# 15_BoardPowerSupply.net
KiCad netlist of a schematic drawn in Altium Designer
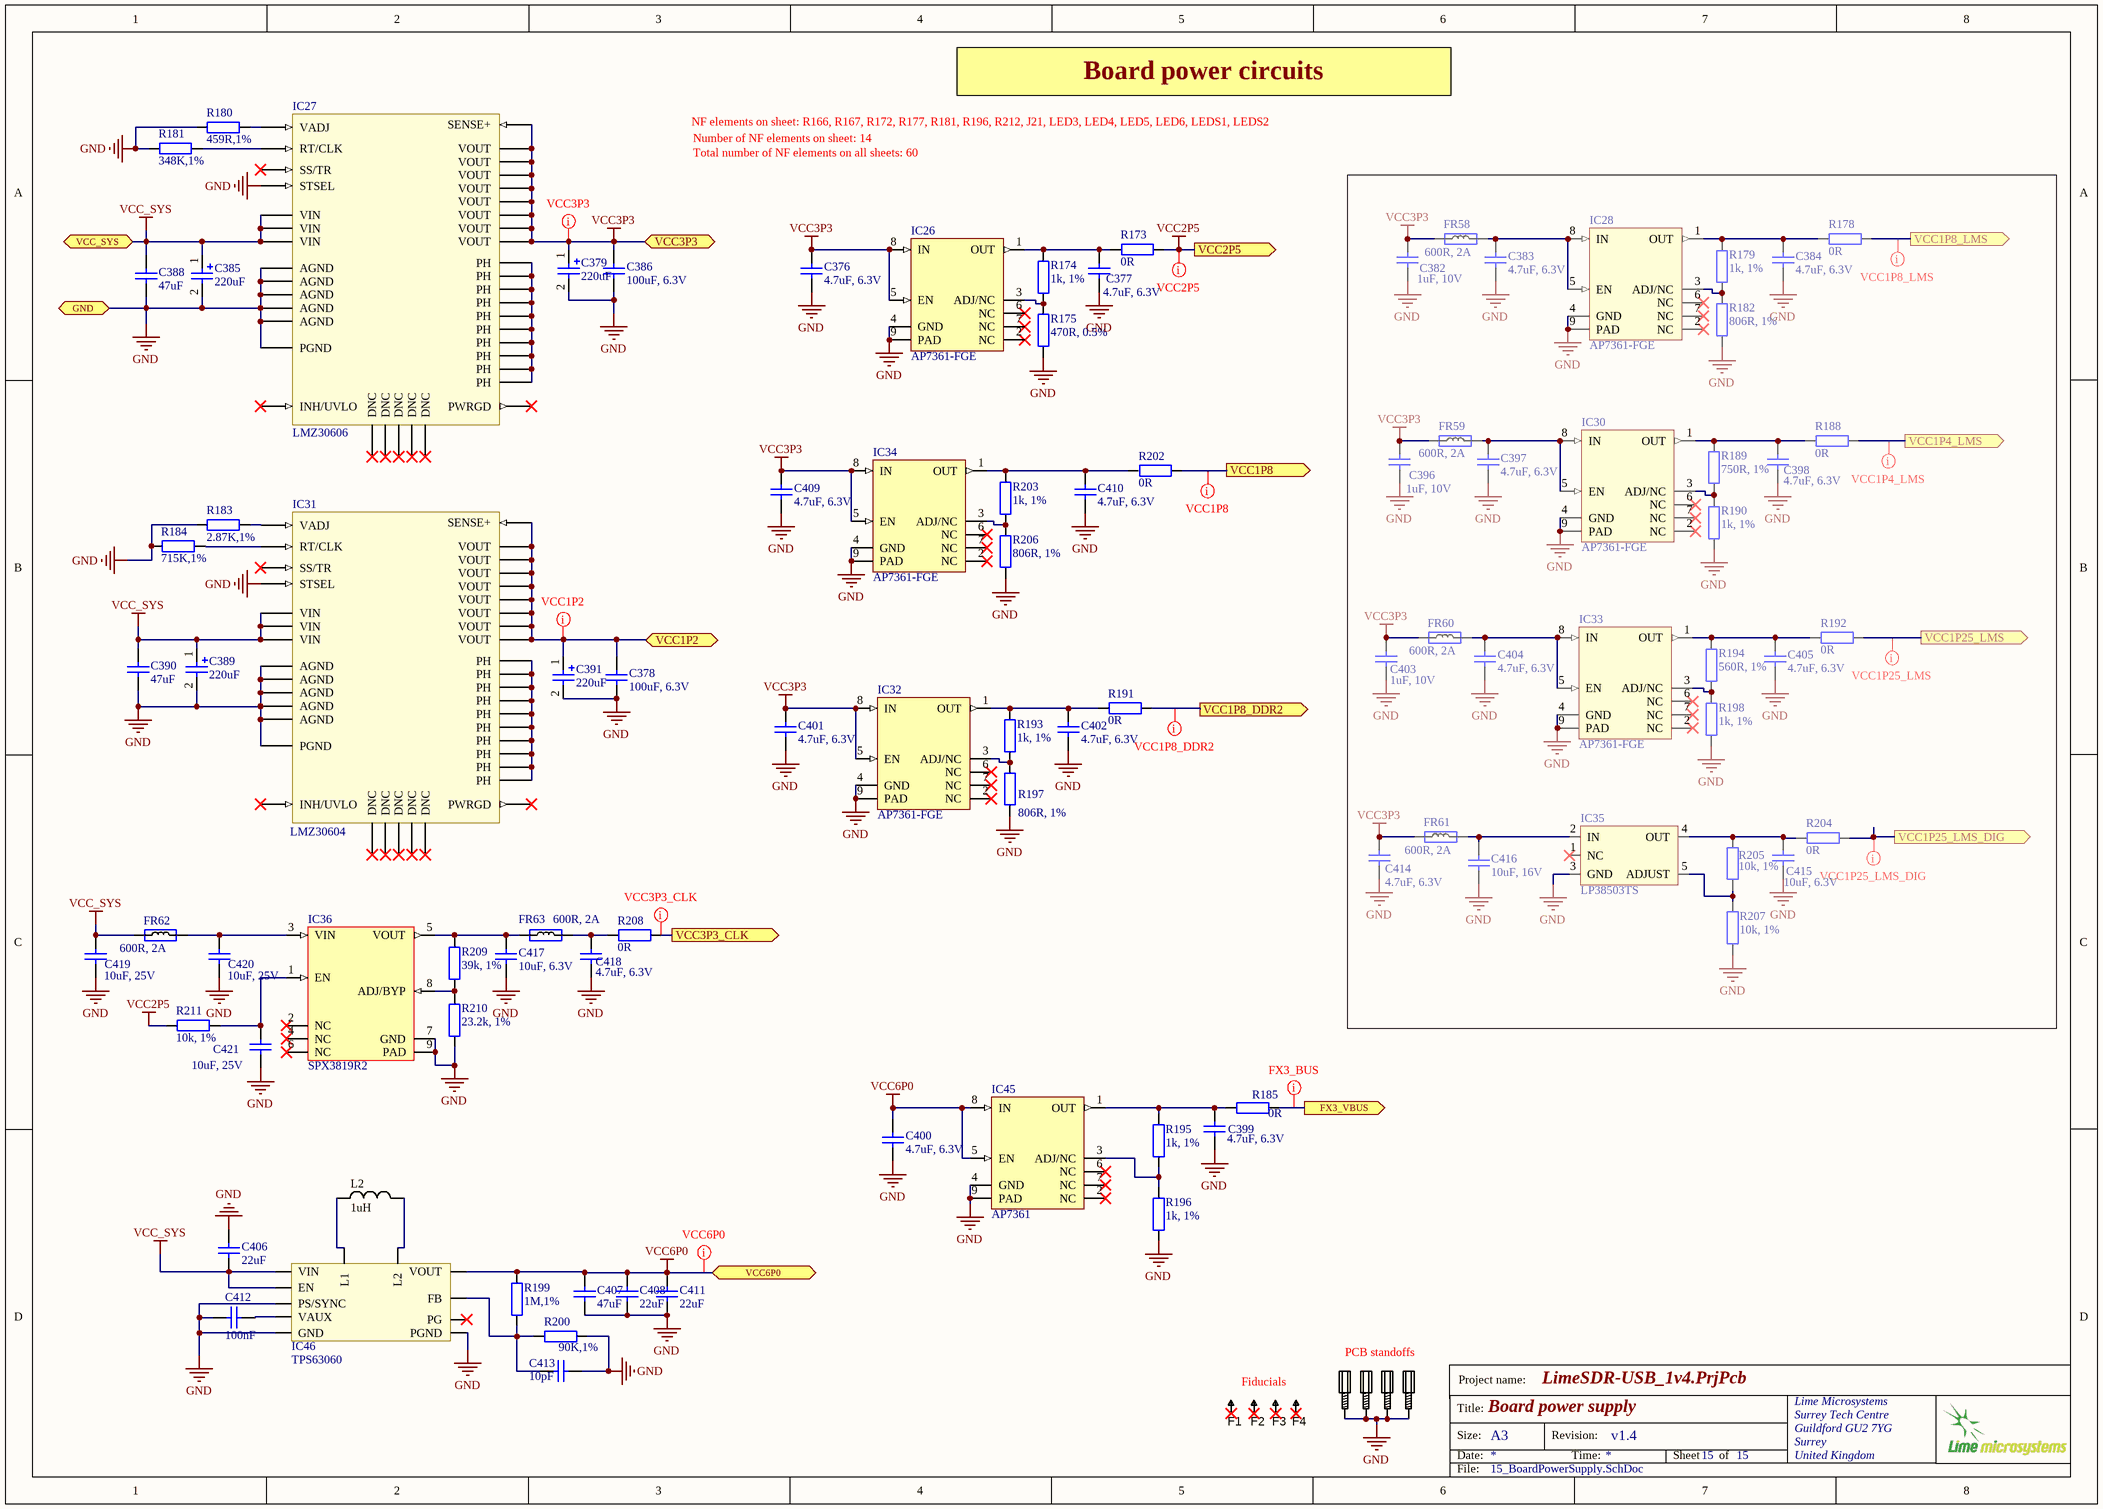
[diagram p0: 15_BoardPowerSupply.SchDoc]

(export (version "E")
  (design (tool "Eeschema 10.0.6"))
  (components
    (comp (ref "C376")
      (value "4.7uF, 6.3V")
      (footprint "CAP0402")
      (fields
        (field (name "MANUFACTURER") "Murata Electronics North America")
        (field (name "TOLERANCE") "±20%")
        (field (name "MANUFACTURER PART NUMBER") "GRM155R60J475ME87D")
      )
      (libsource (lib "LimeMicroAltiumLib_schLib") (part "Cap_0402"))
    )
    (comp (ref "C377")
      (value "4.7uF, 6.3V")
      (footprint "CAP0402")
      (fields
        (field (name "MANUFACTURER") "Murata Electronics North America")
        (field (name "TOLERANCE") "±20%")
        (field (name "MANUFACTURER PART NUMBER") "GRM155R60J475ME87D")
      )
      (libsource (lib "LimeMicroAltiumLib_schLib") (part "Cap_0402"))
    )
    (comp (ref "C378")
      (value "100uF, 6.3V")
      (footprint "CAP1206")
      (fields (field (name "MANUFACTURER") "Murata Electronics North America"))
      (libsource (lib "LimeFPGAboard_schLib") (part "Cap_1206"))
    )
    (comp (ref "C379") (value "220uF") (libsource (lib "LimeMicroAltiumLib_schLib") (part "Cap_pol_1206")))
    (comp (ref "C382")
      (value "1uF, 10V")
      (footprint "CAP0402")
      (fields (field (name "MANUFACTURER") "TDK"))
      (libsource (lib "LimeMicroAltiumLib_schLib") (part "Cap_0402"))
    )
    (comp (ref "C383")
      (value "4.7uF, 6.3V")
      (footprint "CAP0402")
      (fields
        (field (name "MANUFACTURER") "Murata Electronics North America")
        (field (name "TOLERANCE") "±20%")
        (field (name "MANUFACTURER PART NUMBER") "GRM155R60J475ME87D")
      )
      (libsource (lib "LimeMicroAltiumLib_schLib") (part "Cap_0402"))
    )
    (comp (ref "C384")
      (value "4.7uF, 6.3V")
      (footprint "CAP0402")
      (fields
        (field (name "MANUFACTURER") "Murata Electronics North America")
        (field (name "TOLERANCE") "±20%")
        (field (name "MANUFACTURER PART NUMBER") "GRM155R60J475ME87D")
      )
      (libsource (lib "LimeMicroAltiumLib_schLib") (part "Cap_0402"))
    )
    (comp (ref "C385") (value "220uF") (libsource (lib "LimeMicroAltiumLib_schLib") (part "Cap_pol_1206")))
    (comp (ref "C386")
      (value "100uF, 6.3V")
      (footprint "CAP1206")
      (fields (field (name "MANUFACTURER") "Murata Electronics North America"))
      (libsource (lib "LimeFPGAboard_schLib") (part "Cap_1206"))
    )
    (comp (ref "C388")
      (value "47uF")
      (footprint "CAP1206")
      (libsource (lib "LimeMicroAltiumLib_schLib") (part "Cap_1206"))
    )
    (comp (ref "C389") (value "220uF") (libsource (lib "LimeMicroAltiumLib_schLib") (part "Cap_pol_1206")))
    (comp (ref "C390")
      (value "47uF")
      (footprint "CAP1206")
      (fields (field (name "MANUFACTURER") "Murata Electronics North America"))
      (libsource (lib "LimeFPGAboard_schLib") (part "Cap_1206"))
    )
    (comp (ref "C391") (value "220uF") (libsource (lib "LimeMicroAltiumLib_schLib") (part "Cap_pol_1206")))
    (comp (ref "C396")
      (value "1uF, 10V")
      (footprint "CAP0402")
      (fields (field (name "MANUFACTURER") "TDK"))
      (libsource (lib "LimeMicroAltiumLib_schLib") (part "Cap_0402"))
    )
    (comp (ref "C397")
      (value "4.7uF, 6.3V")
      (footprint "CAP0402")
      (fields
        (field (name "MANUFACTURER") "Murata Electronics North America")
        (field (name "TOLERANCE") "±20%")
        (field (name "MANUFACTURER PART NUMBER") "GRM155R60J475ME87D")
      )
      (libsource (lib "LimeMicroAltiumLib_schLib") (part "Cap_0402"))
    )
    (comp (ref "C398")
      (value "4.7uF, 6.3V")
      (footprint "CAP0402")
      (fields
        (field (name "MANUFACTURER") "Murata Electronics North America")
        (field (name "TOLERANCE") "±20%")
        (field (name "MANUFACTURER PART NUMBER") "GRM155R60J475ME87D")
      )
      (libsource (lib "LimeMicroAltiumLib_schLib") (part "Cap_0402"))
    )
    (comp (ref "C399")
      (value "4.7uF, 6.3V")
      (footprint "CAP0402")
      (fields
        (field (name "MANUFACTURER") "Murata Electronics North America")
        (field (name "TOLERANCE") "±20%")
        (field (name "MANUFACTURER PART NUMBER") "GRM155R60J475ME87D")
      )
      (libsource (lib "LimeMicroAltiumLib_schLib") (part "Cap_0402"))
    )
    (comp (ref "C400")
      (value "4.7uF, 6.3V")
      (footprint "CAP0402")
      (fields
        (field (name "MANUFACTURER") "Murata Electronics North America")
        (field (name "TOLERANCE") "±20%")
        (field (name "MANUFACTURER PART NUMBER") "GRM155R60J475ME87D")
      )
      (libsource (lib "LimeMicroAltiumLib_schLib") (part "Cap_0402"))
    )
    (comp (ref "C401")
      (value "4.7uF, 6.3V")
      (footprint "CAP0402")
      (fields
        (field (name "MANUFACTURER") "Murata Electronics North America")
        (field (name "TOLERANCE") "±20%")
        (field (name "MANUFACTURER PART NUMBER") "GRM155R60J475ME87D")
      )
      (libsource (lib "LimeMicroAltiumLib_schLib") (part "Cap_0402"))
    )
    (comp (ref "C402")
      (value "4.7uF, 6.3V")
      (footprint "CAP0402")
      (fields
        (field (name "MANUFACTURER") "Murata Electronics North America")
        (field (name "TOLERANCE") "±20%")
        (field (name "MANUFACTURER PART NUMBER") "GRM155R60J475ME87D")
      )
      (libsource (lib "LimeMicroAltiumLib_schLib") (part "Cap_0402"))
    )
    (comp (ref "C403")
      (value "1uF, 10V")
      (footprint "CAP0402")
      (fields (field (name "MANUFACTURER") "TDK"))
      (libsource (lib "LimeMicroAltiumLib_schLib") (part "Cap_0402"))
    )
    (comp (ref "C404")
      (value "4.7uF, 6.3V")
      (footprint "CAP0402")
      (fields
        (field (name "MANUFACTURER") "Murata Electronics North America")
        (field (name "TOLERANCE") "±20%")
        (field (name "MANUFACTURER PART NUMBER") "GRM155R60J475ME87D")
      )
      (libsource (lib "LimeMicroAltiumLib_schLib") (part "Cap_0402"))
    )
    (comp (ref "C405")
      (value "4.7uF, 6.3V")
      (footprint "CAP0402")
      (fields
        (field (name "MANUFACTURER") "Murata Electronics North America")
        (field (name "TOLERANCE") "±20%")
        (field (name "MANUFACTURER PART NUMBER") "GRM155R60J475ME87D")
      )
      (libsource (lib "LimeMicroAltiumLib_schLib") (part "Cap_0402"))
    )
    (comp (ref "C406")
      (value "22uF")
      (footprint "CAP1206")
      (libsource (lib "LimeMicroAltiumLib_schLib") (part "Cap_1206"))
    )
    (comp (ref "C407")
      (value "47uF")
      (footprint "CAP1206")
      (libsource (lib "LimeMicroAltiumLib_schLib") (part "Cap_1206"))
    )
    (comp (ref "C408")
      (value "22uF")
      (footprint "CAP1206")
      (libsource (lib "LimeMicroAltiumLib_schLib") (part "Cap_1206"))
    )
    (comp (ref "C409")
      (value "4.7uF, 6.3V")
      (footprint "CAP0402")
      (fields
        (field (name "MANUFACTURER") "Murata Electronics North America")
        (field (name "TOLERANCE") "±20%")
        (field (name "MANUFACTURER PART NUMBER") "GRM155R60J475ME87D")
      )
      (libsource (lib "LimeMicroAltiumLib_schLib") (part "Cap_0402"))
    )
    (comp (ref "C410")
      (value "4.7uF, 6.3V")
      (footprint "CAP0402")
      (fields
        (field (name "MANUFACTURER") "Murata Electronics North America")
        (field (name "TOLERANCE") "±20%")
        (field (name "MANUFACTURER PART NUMBER") "GRM155R60J475ME87D")
      )
      (libsource (lib "LimeMicroAltiumLib_schLib") (part "Cap_0402"))
    )
    (comp (ref "C411")
      (value "22uF")
      (footprint "CAP1206")
      (libsource (lib "LimeMicroAltiumLib_schLib") (part "Cap_1206"))
    )
    (comp (ref "C412")
      (value "100nF")
      (footprint "CAP0603")
      (libsource (lib "LimeMicroAltiumLib_schLib") (part "Cap_0603"))
    )
    (comp (ref "C413")
      (value "10pF")
      (footprint "CAP0603")
      (libsource (lib "LimeMicroAltiumLib_schLib") (part "Cap_0603"))
    )
    (comp (ref "C414")
      (value "4.7uF, 6.3V")
      (footprint "CAP0402")
      (fields
        (field (name "MANUFACTURER") "Murata Electronics North America")
        (field (name "TOLERANCE") "±20%")
        (field (name "MANUFACTURER PART NUMBER") "GRM155R60J475ME87D")
      )
      (libsource (lib "LimeMicroAltiumLib_schLib") (part "Cap_0402"))
    )
    (comp (ref "C415")
      (value "10uF, 6.3V")
      (footprint "CAP0603")
      (fields (field (name "TOLERANCE") "±20%") (field (name "MANUFACTURER") "Yageo"))
      (libsource (lib "LimeFPGAboard_schLib") (part "Cap_0603"))
    )
    (comp (ref "C416")
      (value "10uF, 16V")
      (footprint "CAP0603")
      (fields (field (name "MANUFACTURER") "Yageo") (field (name "TOLERANCE") "±20%"))
      (libsource (lib "LimeMicroAltiumLib_schLib") (part "Cap_0603"))
    )
    (comp (ref "C417")
      (value "10uF, 6.3V")
      (footprint "CAP0603")
      (fields (field (name "TOLERANCE") "±20%") (field (name "MANUFACTURER") "Yageo"))
      (libsource (lib "LimeFPGAboard_schLib") (part "Cap_0603"))
    )
    (comp (ref "C418")
      (value "4.7uF, 6.3V")
      (footprint "CAP0402")
      (fields
        (field (name "MANUFACTURER") "Murata Electronics North America")
        (field (name "TOLERANCE") "±20%")
        (field (name "MANUFACTURER PART NUMBER") "GRM155R60J475ME87D")
      )
      (libsource (lib "LimeMicroAltiumLib_schLib") (part "Cap_0402"))
    )
    (comp (ref "C419")
      (value "10uF, 25V")
      (footprint "CAP0603")
      (fields
        (field (name "MANUFACTURER") "Murata Electronics North America")
        (field (name "MANUFACTURER PART NUMBER") "GRM188R61E106MA73D")
        (field (name "TOLERANCE") "±20%")
      )
      (libsource (lib "LimeMicroAltiumLib_schLib") (part "Cap_0603"))
    )
    (comp (ref "C420")
      (value "10uF, 25V")
      (footprint "CAP0603")
      (fields
        (field (name "MANUFACTURER") "Murata Electronics North America")
        (field (name "MANUFACTURER PART NUMBER") "GRM188R61E106MA73D")
        (field (name "TOLERANCE") "±20%")
      )
      (libsource (lib "LimeMicroAltiumLib_schLib") (part "Cap_0603"))
    )
    (comp (ref "C421")
      (value "10uF, 25V")
      (footprint "CAP0603")
      (fields
        (field (name "MANUFACTURER") "Murata Electronics North America")
        (field (name "MANUFACTURER PART NUMBER") "GRM188R61E106MA73D")
        (field (name "TOLERANCE") "±20%")
      )
      (libsource (lib "LimeMicroAltiumLib_schLib") (part "Cap_0603"))
    )
    (comp (ref "F1")
      (value "Fiducial")
      (footprint "Fiducial")
      (libsource (lib "VGTU_Altium_lib") (part "Fiducial"))
    )
    (comp (ref "F2")
      (value "Fiducial")
      (footprint "Fiducial")
      (libsource (lib "VGTU_Altium_lib") (part "Fiducial"))
    )
    (comp (ref "F3")
      (value "Fiducial")
      (footprint "Fiducial")
      (libsource (lib "VGTU_Altium_lib") (part "Fiducial"))
    )
    (comp (ref "F4")
      (value "Fiducial")
      (footprint "Fiducial")
      (libsource (lib "VGTU_Altium_lib") (part "Fiducial"))
    )
    (comp (ref "FR58")
      (value "600R, 2A")
      (footprint "RES0805")
      (fields (field (name "MANUFACTURER") "TDK Corporation"))
      (libsource (lib "LimeMicroAltiumLib_schLib") (part "Ferrite"))
    )
    (comp (ref "FR59")
      (value "600R, 2A")
      (footprint "RES0805")
      (fields (field (name "MANUFACTURER") "TDK Corporation"))
      (libsource (lib "LimeMicroAltiumLib_schLib") (part "Ferrite"))
    )
    (comp (ref "FR60")
      (value "600R, 2A")
      (footprint "RES0805")
      (fields (field (name "MANUFACTURER") "TDK Corporation"))
      (libsource (lib "LimeMicroAltiumLib_schLib") (part "Ferrite"))
    )
    (comp (ref "FR61")
      (value "600R, 2A")
      (footprint "RES0805")
      (fields (field (name "MANUFACTURER") "TDK Corporation"))
      (libsource (lib "LimeMicroAltiumLib_schLib") (part "Ferrite"))
    )
    (comp (ref "FR62")
      (value "600R, 2A")
      (footprint "RES0805")
      (fields (field (name "MANUFACTURER") "TDK Corporation"))
      (libsource (lib "LimeMicroAltiumLib_schLib") (part "Ferrite"))
    )
    (comp (ref "FR63")
      (value "600R, 2A")
      (footprint "RES0805")
      (fields (field (name "MANUFACTURER") "TDK Corporation"))
      (libsource (lib "LimeMicroAltiumLib_schLib") (part "Ferrite"))
    )
    (comp (ref "IC26")
      (value "AP7361-FGE")
      (footprint "AP7361")
      (fields
        (field (name "MANUFACTURER PART NUMBER") "AP7361-FGE-7")
        (field (name "MANUFACTURER") "Diodes Incorporated")
      )
      (libsource (lib "LimeMicroAltiumLib_schLib") (part "AP7361"))
    )
    (comp (ref "IC27")
      (value "LMZ30606")
      (footprint "QFN-LMZ306xx")
      (libsource (lib "LimeMicroAltiumLib_schLib") (part "LMZ30606"))
    )
    (comp (ref "IC28")
      (value "AP7361-FGE")
      (footprint "AP7361")
      (fields
        (field (name "MANUFACTURER PART NUMBER") "AP7361-FGE-7")
        (field (name "MANUFACTURER") "Diodes Incorporated")
      )
      (libsource (lib "LimeMicroAltiumLib_schLib") (part "AP7361"))
    )
    (comp (ref "IC30")
      (value "AP7361-FGE")
      (footprint "AP7361")
      (fields
        (field (name "MANUFACTURER PART NUMBER") "AP7361-FGE-7")
        (field (name "MANUFACTURER") "Diodes Incorporated")
      )
      (libsource (lib "LimeMicroAltiumLib_schLib") (part "AP7361"))
    )
    (comp (ref "IC31")
      (value "LMZ30604")
      (footprint "QFN-LMZ306xx")
      (libsource (lib "LimeMicroAltiumLib_schLib") (part "LMZ30604"))
    )
    (comp (ref "IC32")
      (value "AP7361-FGE")
      (footprint "AP7361")
      (fields
        (field (name "MANUFACTURER PART NUMBER") "AP7361-FGE-7")
        (field (name "MANUFACTURER") "Diodes Incorporated")
      )
      (libsource (lib "LimeMicroAltiumLib_schLib") (part "AP7361"))
    )
    (comp (ref "IC33")
      (value "AP7361-FGE")
      (footprint "AP7361")
      (fields
        (field (name "MANUFACTURER PART NUMBER") "AP7361-FGE-7")
        (field (name "MANUFACTURER") "Diodes Incorporated")
      )
      (libsource (lib "LimeMicroAltiumLib_schLib") (part "AP7361"))
    )
    (comp (ref "IC34")
      (value "AP7361-FGE")
      (footprint "AP7361")
      (fields
        (field (name "MANUFACTURER PART NUMBER") "AP7361-FGE-7")
        (field (name "MANUFACTURER") "Diodes Incorporated")
      )
      (libsource (lib "LimeMicroAltiumLib_schLib") (part "AP7361"))
    )
    (comp (ref "IC35")
      (value "LP38503TS")
      (footprint "TO-263-5_v2")
      (fields
        (field (name "MANUFACTURER PART NUMBER") "LP38503TS-ADJ/NOPB")
        (field (name "MANUFACTURER") "Texas Instruments")
      )
      (libsource (lib "LimeMicroAltiumLib_schLib") (part "LP38503TS"))
    )
    (comp (ref "IC36")
      (value "SPX3819R2")
      (footprint "SPX3819R2-L/TR")
      (fields (field (name "MANUFACTURER") "Exar Corporation"))
      (libsource (lib "LimeMicroAltiumLib_schLib") (part "SPX3819R2-L/TR"))
    )
    (comp (ref "IC45")
      (value "AP7361")
      (footprint "AP7361")
      (fields (field (name "MANUFACTURER") "Diodes Incorporated"))
      (libsource (lib "LimeMicroAltiumLib_schLib") (part "AP7361"))
    )
    (comp (ref "IC46")
      (value "TPS63060")
      (footprint "SON-10")
      (libsource (lib "LimeMicroAltiumLib_schLib") (part "TPS63060"))
    )
    (comp (ref "L2")
      (value "1uH")
      (footprint "FDVE1040_TOKO_INDUCTOR")
      (fields (field (name "TOLERANCE") "±20%") (field (name "MANUFACTURER") "Vishay Dale"))
      (libsource (lib "LimeMicroAltiumLib_schLib") (part "Inductor_0603"))
    )
    (comp (ref "MECH1")
      (value "# pcs.")
      (footprint "PCB_standoff")
      (description "STANDOFF M/F MET 5MM HEX 10MM L")
      (fields (field (name "MANUFACTURER") "FIX&FASTEN"))
      (libsource (lib "LimeMicroAltiumLib_schLib") (part "STANDOFF_M-F_THREADED_M3x8x10mm_HEX_5mm dia"))
    )
    (comp (ref "MECH2")
      (value "# pcs.")
      (footprint "PCB_standoff")
      (description "STANDOFF M/F MET 5MM HEX 10MM L")
      (fields (field (name "MANUFACTURER") "FIX&FASTEN"))
      (libsource (lib "LimeMicroAltiumLib_schLib") (part "STANDOFF_M-F_THREADED_M3x8x10mm_HEX_5mm dia"))
    )
    (comp (ref "MECH3")
      (value "# pcs.")
      (footprint "PCB_standoff")
      (description "STANDOFF M/F MET 5MM HEX 10MM L")
      (fields (field (name "MANUFACTURER") "FIX&FASTEN"))
      (libsource (lib "LimeMicroAltiumLib_schLib") (part "STANDOFF_M-F_THREADED_M3x8x10mm_HEX_5mm dia"))
    )
    (comp (ref "MECH4")
      (value "# pcs.")
      (footprint "PCB_standoff")
      (description "STANDOFF M/F MET 5MM HEX 10MM L")
      (fields (field (name "MANUFACTURER") "FIX&FASTEN"))
      (libsource (lib "LimeMicroAltiumLib_schLib") (part "STANDOFF_M-F_THREADED_M3x8x10mm_HEX_5mm dia"))
    )
    (comp (ref "R173")
      (value "0R")
      (footprint "RES0402")
      (fields (field (name "MANUFACTURER") "Yageo") (field (name "TOLERANCE") "Jumper"))
      (libsource (lib "LimeMicroAltiumLib_schLib") (part "Res_0402"))
    )
    (comp (ref "R174")
      (value "1k, 1%")
      (footprint "RES0402")
      (fields (field (name "MANUFACTURER") "Stackpole Electronics Inc") (field (name "TOLERANCE") "±1%"))
      (libsource (lib "LimeMicroAltiumLib_schLib") (part "Res_0402"))
    )
    (comp (ref "R175")
      (value "470R, 0.5%")
      (footprint "RES0402")
      (fields
        (field (name "TOLERANCE") "±0.5%")
        (field (name "MANUFACTURER") "Panasonic Electronic Components")
      )
      (libsource (lib "LimeMicroAltiumLib_schLib") (part "Res_0402"))
    )
    (comp (ref "R178")
      (value "0R")
      (footprint "RES0402")
      (fields (field (name "MANUFACTURER") "Yageo") (field (name "TOLERANCE") "Jumper"))
      (libsource (lib "LimeMicroAltiumLib_schLib") (part "Res_0402"))
    )
    (comp (ref "R179")
      (value "1k, 1%")
      (footprint "RES0402")
      (fields (field (name "MANUFACTURER") "Stackpole Electronics Inc") (field (name "TOLERANCE") "±1%"))
      (libsource (lib "LimeMicroAltiumLib_schLib") (part "Res_0402"))
    )
    (comp (ref "R180")
      (value "459R,1%")
      (footprint "RES0402")
      (fields (field (name "MANUFACTURER") "Yageo") (field (name "TOLERANCE") "±1%"))
      (libsource (lib "LimeMicroAltiumLib_schLib") (part "Res_0402"))
    )
    (comp (ref "R181")
      (value "348K,1%")
      (footprint "RES0402")
      (fields (field (name "MANUFACTURER") "Yageo") (field (name "TOLERANCE") "±1%"))
      (libsource (lib "LimeMicroAltiumLib_schLib") (part "Res_0402"))
    )
    (comp (ref "R182")
      (value "806R, 1%")
      (footprint "RES0402")
      (fields (field (name "TOLERANCE") "±1%") (field (name "MANUFACTURER") "Stackpole Electronics Inc"))
      (libsource (lib "LimeMicroAltiumLib_schLib") (part "Res_0402"))
    )
    (comp (ref "R183")
      (value "2.87K,1%")
      (footprint "RES0402")
      (fields (field (name "MANUFACTURER") "Yageo") (field (name "TOLERANCE") "±1%"))
      (libsource (lib "LimeMicroAltiumLib_schLib") (part "Res_0402"))
    )
    (comp (ref "R184")
      (value "715K,1%")
      (footprint "RES0402")
      (fields (field (name "MANUFACTURER") "Yageo") (field (name "TOLERANCE") "±1%"))
      (libsource (lib "LimeMicroAltiumLib_schLib") (part "Res_0402"))
    )
    (comp (ref "R185")
      (value "0R")
      (footprint "RES0402")
      (fields (field (name "MANUFACTURER") "Yageo") (field (name "TOLERANCE") "Jumper"))
      (libsource (lib "LimeMicroAltiumLib_schLib") (part "Res_0402"))
    )
    (comp (ref "R188")
      (value "0R")
      (footprint "RES0402")
      (fields (field (name "MANUFACTURER") "Yageo") (field (name "TOLERANCE") "Jumper"))
      (libsource (lib "LimeMicroAltiumLib_schLib") (part "Res_0402"))
    )
    (comp (ref "R189")
      (value "750R, 1%")
      (footprint "RES0402")
      (fields
        (field (name "TOLERANCE") "±1%")
        (field (name "MANUFACTURER PART NUMBER") "RC0402FR-07750RL")
        (field (name "MANUFACTURER") "Yageo")
      )
      (libsource (lib "LimeMicroAltiumLib_schLib") (part "Res_0402"))
    )
    (comp (ref "R190")
      (value "1k, 1%")
      (footprint "RES0402")
      (fields (field (name "MANUFACTURER") "Stackpole Electronics Inc") (field (name "TOLERANCE") "±1%"))
      (libsource (lib "LimeMicroAltiumLib_schLib") (part "Res_0402"))
    )
    (comp (ref "R191")
      (value "0R")
      (footprint "RES0402")
      (fields (field (name "MANUFACTURER") "Yageo") (field (name "TOLERANCE") "Jumper"))
      (libsource (lib "LimeMicroAltiumLib_schLib") (part "Res_0402"))
    )
    (comp (ref "R192")
      (value "0R")
      (footprint "RES0402")
      (fields (field (name "MANUFACTURER") "Yageo") (field (name "TOLERANCE") "Jumper"))
      (libsource (lib "LimeMicroAltiumLib_schLib") (part "Res_0402"))
    )
    (comp (ref "R193")
      (value "1k, 1%")
      (footprint "RES0402")
      (fields (field (name "MANUFACTURER") "Stackpole Electronics Inc") (field (name "TOLERANCE") "±1%"))
      (libsource (lib "LimeMicroAltiumLib_schLib") (part "Res_0402"))
    )
    (comp (ref "R194")
      (value "560R, 1%")
      (footprint "RES0402")
      (fields
        (field (name "MANUFACTURER PART NUMBER") "CRCW0402560RFKED")
        (field (name "TOLERANCE") "±1%")
        (field (name "MANUFACTURER") "Vishay Dale")
      )
      (libsource (lib "LimeMicroAltiumLib_schLib") (part "Res_0402"))
    )
    (comp (ref "R195")
      (value "1k, 1%")
      (footprint "RES0402")
      (fields (field (name "MANUFACTURER") "Stackpole Electronics Inc") (field (name "TOLERANCE") "±1%"))
      (libsource (lib "LimeMicroAltiumLib_schLib") (part "Res_0402"))
    )
    (comp (ref "R196")
      (value "1k, 1%")
      (footprint "RES0402")
      (fields (field (name "MANUFACTURER") "Stackpole Electronics Inc") (field (name "TOLERANCE") "±1%"))
      (libsource (lib "LimeMicroAltiumLib_schLib") (part "Res_0402"))
    )
    (comp (ref "R197")
      (value "806R, 1%")
      (footprint "RES0402")
      (fields (field (name "TOLERANCE") "±1%") (field (name "MANUFACTURER") "Stackpole Electronics Inc"))
      (libsource (lib "LimeMicroAltiumLib_schLib") (part "Res_0402"))
    )
    (comp (ref "R198")
      (value "1k, 1%")
      (footprint "RES0402")
      (fields (field (name "MANUFACTURER") "Stackpole Electronics Inc") (field (name "TOLERANCE") "±1%"))
      (libsource (lib "LimeMicroAltiumLib_schLib") (part "Res_0402"))
    )
    (comp (ref "R199")
      (value "1M,1%")
      (footprint "RES0402")
      (fields (field (name "MANUFACTURER") "Stackpole Electronics Inc") (field (name "TOLERANCE") "±1%"))
      (libsource (lib "LimeMicroAltiumLib_schLib") (part "Res_0402"))
    )
    (comp (ref "R200")
      (value "90K,1%")
      (footprint "RES0402")
      (fields (field (name "MANUFACTURER") "Stackpole Electronics Inc") (field (name "TOLERANCE") "±1%"))
      (libsource (lib "LimeMicroAltiumLib_schLib") (part "Res_0402"))
    )
    (comp (ref "R202")
      (value "0R")
      (footprint "RES0402")
      (fields (field (name "MANUFACTURER") "Yageo") (field (name "TOLERANCE") "Jumper"))
      (libsource (lib "LimeMicroAltiumLib_schLib") (part "Res_0402"))
    )
    (comp (ref "R203")
      (value "1k, 1%")
      (footprint "RES0402")
      (fields (field (name "MANUFACTURER") "Stackpole Electronics Inc") (field (name "TOLERANCE") "±1%"))
      (libsource (lib "LimeMicroAltiumLib_schLib") (part "Res_0402"))
    )
    (comp (ref "R204")
      (value "0R")
      (footprint "RES0402")
      (fields (field (name "MANUFACTURER") "Yageo") (field (name "TOLERANCE") "Jumper"))
      (libsource (lib "LimeMicroAltiumLib_schLib") (part "Res_0402"))
    )
    (comp (ref "R205")
      (value "10k, 1%")
      (footprint "RES0402")
      (fields (field (name "MANUFACTURER") "Yageo") (field (name "TOLERANCE") "±1%"))
      (libsource (lib "LimeMicroAltiumLib_schLib") (part "Res_0402"))
    )
    (comp (ref "R206")
      (value "806R, 1%")
      (footprint "RES0402")
      (fields (field (name "TOLERANCE") "±1%") (field (name "MANUFACTURER") "Stackpole Electronics Inc"))
      (libsource (lib "LimeMicroAltiumLib_schLib") (part "Res_0402"))
    )
    (comp (ref "R207")
      (value "10k, 1%")
      (footprint "RES0402")
      (fields (field (name "MANUFACTURER") "Yageo") (field (name "TOLERANCE") "±1%"))
      (libsource (lib "LimeMicroAltiumLib_schLib") (part "Res_0402"))
    )
    (comp (ref "R208")
      (value "0R")
      (footprint "RES0402")
      (fields (field (name "MANUFACTURER") "Yageo") (field (name "TOLERANCE") "Jumper"))
      (libsource (lib "LimeMicroAltiumLib_schLib") (part "Res_0402"))
    )
    (comp (ref "R209")
      (value "39k, 1%")
      (footprint "RES0402")
      (fields (field (name "MANUFACTURER") "Yageo") (field (name "TOLERANCE") "±1%"))
      (libsource (lib "LimeMicroAltiumLib_schLib") (part "Res_0402"))
    )
    (comp (ref "R210")
      (value "23.2k, 1%")
      (footprint "RES0402")
      (fields (field (name "TOLERANCE") "±1%") (field (name "MANUFACTURER") "Yageo"))
      (libsource (lib "LimeMicroAltiumLib_schLib") (part "Res_0402"))
    )
    (comp (ref "R211")
      (value "10k, 1%")
      (footprint "RES0402")
      (fields (field (name "MANUFACTURER") "Yageo") (field (name "TOLERANCE") "±1%"))
      (libsource (lib "LimeMicroAltiumLib_schLib") (part "Res_0402"))
    )
  )
  (nets
    (net (code "1") (name "/FX3_VBUS") (class "Default")
      (node (ref "R185") (pin "1") (pinfunction "1_1") (pintype "passive"))
    )
    (net (code "2") (name "/VCC1P2") (class "Default")
      (node (ref "C378") (pin "2") (pinfunction "2_2") (pintype "passive"))
      (node (ref "C391") (pin "1") (pinfunction "1_1") (pintype "passive"))
      (node (ref "IC31") (pin "10") (pinfunction "VOUT_10") (pintype "power_in"))
      (node (ref "IC31") (pin "11") (pinfunction "VOUT_11") (pintype "power_in"))
      (node (ref "IC31") (pin "12") (pinfunction "VOUT_12") (pintype "power_in"))
      (node (ref "IC31") (pin "13") (pinfunction "VOUT_13") (pintype "power_in"))
      (node (ref "IC31") (pin "14") (pinfunction "VOUT_14") (pintype "power_in"))
      (node (ref "IC31") (pin "36") (pinfunction "SENSE+_36") (pintype "input"))
      (node (ref "IC31") (pin "38") (pinfunction "VOUT_38") (pintype "power_in"))
      (node (ref "IC31") (pin "8") (pinfunction "VOUT_8") (pintype "power_in"))
      (node (ref "IC31") (pin "9") (pinfunction "VOUT_9") (pintype "power_in"))
    )
    (net (code "3") (name "/VCC1P4_LMS") (class "Default")
      (node (ref "R188") (pin "1") (pinfunction "1_1") (pintype "passive"))
    )
    (net (code "4") (name "/VCC1P8") (class "Default")
      (node (ref "R202") (pin "1") (pinfunction "1_1") (pintype "passive"))
    )
    (net (code "5") (name "/VCC1P8_DDR2") (class "Default")
      (node (ref "R191") (pin "1") (pinfunction "1_1") (pintype "passive"))
    )
    (net (code "6") (name "/VCC1P8_LMS") (class "Default")
      (node (ref "R178") (pin "1") (pinfunction "1_1") (pintype "passive"))
    )
    (net (code "7") (name "/VCC1P25_LMS") (class "Default")
      (node (ref "R192") (pin "1") (pinfunction "1_1") (pintype "passive"))
    )
    (net (code "8") (name "/VCC1P25_LMS_DIG") (class "Default")
      (node (ref "R204") (pin "1") (pinfunction "1_1") (pintype "passive"))
    )
    (net (code "9") (name "/VCC3P3_CLK") (class "Default")
      (node (ref "R208") (pin "1") (pinfunction "1_1") (pintype "passive"))
    )
    (net (code "10") (name "GND") (class "Default")
      (node (ref "C376") (pin "1") (pinfunction "1_1") (pintype "passive"))
      (node (ref "C377") (pin "1") (pinfunction "1_1") (pintype "passive"))
      (node (ref "C378") (pin "1") (pinfunction "1_1") (pintype "passive"))
      (node (ref "C379") (pin "2") (pinfunction "2_2") (pintype "passive"))
      (node (ref "C382") (pin "1") (pinfunction "1_1") (pintype "passive"))
      (node (ref "C383") (pin "1") (pinfunction "1_1") (pintype "passive"))
      (node (ref "C384") (pin "1") (pinfunction "1_1") (pintype "passive"))
      (node (ref "C385") (pin "2") (pinfunction "2_2") (pintype "passive"))
      (node (ref "C386") (pin "1") (pinfunction "1_1") (pintype "passive"))
      (node (ref "C388") (pin "1") (pinfunction "1_1") (pintype "passive"))
      (node (ref "C389") (pin "2") (pinfunction "2_2") (pintype "passive"))
      (node (ref "C390") (pin "1") (pinfunction "1_1") (pintype "passive"))
      (node (ref "C391") (pin "2") (pinfunction "2_2") (pintype "passive"))
      (node (ref "C396") (pin "1") (pinfunction "1_1") (pintype "passive"))
      (node (ref "C397") (pin "1") (pinfunction "1_1") (pintype "passive"))
      (node (ref "C398") (pin "1") (pinfunction "1_1") (pintype "passive"))
      (node (ref "C399") (pin "1") (pinfunction "1_1") (pintype "passive"))
      (node (ref "C400") (pin "1") (pinfunction "1_1") (pintype "passive"))
      (node (ref "C401") (pin "1") (pinfunction "1_1") (pintype "passive"))
      (node (ref "C402") (pin "1") (pinfunction "1_1") (pintype "passive"))
      (node (ref "C403") (pin "1") (pinfunction "1_1") (pintype "passive"))
      (node (ref "C404") (pin "1") (pinfunction "1_1") (pintype "passive"))
      (node (ref "C405") (pin "1") (pinfunction "1_1") (pintype "passive"))
      (node (ref "C406") (pin "2") (pinfunction "2_2") (pintype "passive"))
      (node (ref "C407") (pin "1") (pinfunction "1_1") (pintype "passive"))
      (node (ref "C408") (pin "1") (pinfunction "1_1") (pintype "passive"))
      (node (ref "C409") (pin "1") (pinfunction "1_1") (pintype "passive"))
      (node (ref "C410") (pin "1") (pinfunction "1_1") (pintype "passive"))
      (node (ref "C411") (pin "1") (pinfunction "1_1") (pintype "passive"))
      (node (ref "C412") (pin "1") (pinfunction "1_1") (pintype "passive"))
      (node (ref "C413") (pin "2") (pinfunction "2_2") (pintype "passive"))
      (node (ref "C414") (pin "1") (pinfunction "1_1") (pintype "passive"))
      (node (ref "C415") (pin "1") (pinfunction "1_1") (pintype "passive"))
      (node (ref "C416") (pin "1") (pinfunction "1_1") (pintype "passive"))
      (node (ref "C417") (pin "1") (pinfunction "1_1") (pintype "passive"))
      (node (ref "C418") (pin "1") (pinfunction "1_1") (pintype "passive"))
      (node (ref "C419") (pin "1") (pinfunction "1_1") (pintype "passive"))
      (node (ref "C420") (pin "1") (pinfunction "1_1") (pintype "passive"))
      (node (ref "C421") (pin "1") (pinfunction "1_1") (pintype "passive"))
      (node (ref "IC26") (pin "4") (pinfunction "GND_4") (pintype "passive"))
      (node (ref "IC26") (pin "9") (pinfunction "PAD_9") (pintype "passive"))
      (node (ref "IC27") (pin "1") (pinfunction "AGND_1") (pintype "power_in"))
      (node (ref "IC27") (pin "29") (pinfunction "AGND_29") (pintype "power_in"))
      (node (ref "IC27") (pin "33") (pinfunction "AGND_33") (pintype "power_in"))
      (node (ref "IC27") (pin "34") (pinfunction "AGND_34") (pintype "power_in"))
      (node (ref "IC27") (pin "37") (pinfunction "PGND_37") (pintype "power_in"))
      (node (ref "IC27") (pin "5") (pinfunction "AGND_5") (pintype "power_in"))
      (node (ref "IC27") (pin "7") (pinfunction "STSEL_7") (pintype "input"))
      (node (ref "IC28") (pin "4") (pinfunction "GND_4") (pintype "passive"))
      (node (ref "IC28") (pin "9") (pinfunction "PAD_9") (pintype "passive"))
      (node (ref "IC30") (pin "4") (pinfunction "GND_4") (pintype "passive"))
      (node (ref "IC30") (pin "9") (pinfunction "PAD_9") (pintype "passive"))
      (node (ref "IC31") (pin "1") (pinfunction "AGND_1") (pintype "power_in"))
      (node (ref "IC31") (pin "29") (pinfunction "AGND_29") (pintype "power_in"))
      (node (ref "IC31") (pin "33") (pinfunction "AGND_33") (pintype "power_in"))
      (node (ref "IC31") (pin "34") (pinfunction "AGND_34") (pintype "power_in"))
      (node (ref "IC31") (pin "37") (pinfunction "PGND_37") (pintype "power_in"))
      (node (ref "IC31") (pin "5") (pinfunction "AGND_5") (pintype "power_in"))
      (node (ref "IC31") (pin "7") (pinfunction "STSEL_7") (pintype "input"))
      (node (ref "IC32") (pin "4") (pinfunction "GND_4") (pintype "passive"))
      (node (ref "IC32") (pin "9") (pinfunction "PAD_9") (pintype "passive"))
      (node (ref "IC33") (pin "4") (pinfunction "GND_4") (pintype "passive"))
      (node (ref "IC33") (pin "9") (pinfunction "PAD_9") (pintype "passive"))
      (node (ref "IC34") (pin "4") (pinfunction "GND_4") (pintype "passive"))
      (node (ref "IC34") (pin "9") (pinfunction "PAD_9") (pintype "passive"))
      (node (ref "IC35") (pin "3") (pinfunction "GND_3") (pintype "passive"))
      (node (ref "IC36") (pin "7") (pinfunction "GND_7") (pintype "passive"))
      (node (ref "IC36") (pin "9") (pinfunction "PAD_9") (pintype "passive"))
      (node (ref "IC45") (pin "4") (pinfunction "GND_4") (pintype "passive"))
      (node (ref "IC45") (pin "9") (pinfunction "PAD_9") (pintype "passive"))
      (node (ref "IC46") (pin "4") (pinfunction "PS/SYNC_4") (pintype "power_in"))
      (node (ref "IC46") (pin "7") (pinfunction "GND_7") (pintype "power_in"))
      (node (ref "IC46") (pin "pp") (pinfunction "PGND_pp") (pintype "power_in"))
      (node (ref "MECH1") (pin "MH1") (pinfunction "MH1_MH1") (pintype "passive"))
      (node (ref "MECH2") (pin "MH1") (pinfunction "MH1_MH1") (pintype "passive"))
      (node (ref "MECH3") (pin "MH1") (pinfunction "MH1_MH1") (pintype "passive"))
      (node (ref "MECH4") (pin "MH1") (pinfunction "MH1_MH1") (pintype "passive"))
      (node (ref "R175") (pin "2") (pinfunction "2_2") (pintype "passive"))
      (node (ref "R180") (pin "1") (pinfunction "1_1") (pintype "passive"))
      (node (ref "R181") (pin "1") (pinfunction "1_1") (pintype "passive"))
      (node (ref "R182") (pin "2") (pinfunction "2_2") (pintype "passive"))
      (node (ref "R183") (pin "1") (pinfunction "1_1") (pintype "passive"))
      (node (ref "R184") (pin "1") (pinfunction "1_1") (pintype "passive"))
      (node (ref "R190") (pin "1") (pinfunction "1_1") (pintype "passive"))
      (node (ref "R196") (pin "1") (pinfunction "1_1") (pintype "passive"))
      (node (ref "R197") (pin "2") (pinfunction "2_2") (pintype "passive"))
      (node (ref "R198") (pin "1") (pinfunction "1_1") (pintype "passive"))
      (node (ref "R200") (pin "1") (pinfunction "1_1") (pintype "passive"))
      (node (ref "R206") (pin "2") (pinfunction "2_2") (pintype "passive"))
      (node (ref "R207") (pin "2") (pinfunction "2_2") (pintype "passive"))
      (node (ref "R210") (pin "1") (pinfunction "1_1") (pintype "passive"))
    )
    (net (code "11") (name "Net-(C418-Pad2)") (class "Default")
      (node (ref "C418") (pin "2") (pinfunction "2_2") (pintype "passive"))
      (node (ref "FR63") (pin "2") (pinfunction "2_2") (pintype "passive"))
      (node (ref "R208") (pin "2") (pinfunction "2_2") (pintype "passive"))
    )
    (net (code "12") (name "Net-(IC26-ADJ{slash}NC)") (class "Default")
      (node (ref "IC26") (pin "3") (pinfunction "ADJ/NC_3") (pintype "passive"))
      (node (ref "R174") (pin "1") (pinfunction "1_1") (pintype "passive"))
      (node (ref "R175") (pin "1") (pinfunction "1_1") (pintype "passive"))
    )
    (net (code "13") (name "Net-(IC26-OUT)") (class "Default")
      (node (ref "C377") (pin "2") (pinfunction "2_2") (pintype "passive"))
      (node (ref "IC26") (pin "1") (pinfunction "OUT_1") (pintype "output"))
      (node (ref "R173") (pin "2") (pinfunction "2_2") (pintype "passive"))
      (node (ref "R174") (pin "2") (pinfunction "2_2") (pintype "passive"))
    )
    (net (code "14") (name "Net-(IC27-PH-Pad17)") (class "Default")
      (node (ref "IC27") (pin "17") (pinfunction "PH_17") (pintype "power_in"))
      (node (ref "IC27") (pin "18") (pinfunction "PH_18") (pintype "power_in"))
      (node (ref "IC27") (pin "19") (pinfunction "PH_19") (pintype "power_in"))
      (node (ref "IC27") (pin "20") (pinfunction "PH_20") (pintype "power_in"))
      (node (ref "IC27") (pin "21") (pinfunction "PH_21") (pintype "power_in"))
      (node (ref "IC27") (pin "22") (pinfunction "PH_22") (pintype "power_in"))
      (node (ref "IC27") (pin "23") (pinfunction "PH_23") (pintype "power_in"))
      (node (ref "IC27") (pin "24") (pinfunction "PH_24") (pintype "power_in"))
      (node (ref "IC27") (pin "25") (pinfunction "PH_25") (pintype "power_in"))
      (node (ref "IC27") (pin "39") (pinfunction "PH_39") (pintype "power_in"))
    )
    (net (code "15") (name "Net-(IC27-RT{slash}CLK)") (class "Default")
      (node (ref "IC27") (pin "4") (pinfunction "RT/CLK_4") (pintype "input"))
      (node (ref "R181") (pin "2") (pinfunction "2_2") (pintype "passive"))
    )
    (net (code "16") (name "Net-(IC27-VADJ)") (class "Default")
      (node (ref "IC27") (pin "35") (pinfunction "VADJ_35") (pintype "input"))
      (node (ref "R180") (pin "2") (pinfunction "2_2") (pintype "passive"))
    )
    (net (code "17") (name "Net-(IC28-ADJ{slash}NC)") (class "Default")
      (node (ref "IC28") (pin "3") (pinfunction "ADJ/NC_3") (pintype "passive"))
      (node (ref "R179") (pin "1") (pinfunction "1_1") (pintype "passive"))
      (node (ref "R182") (pin "1") (pinfunction "1_1") (pintype "passive"))
    )
    (net (code "18") (name "Net-(IC28-EN)") (class "Default")
      (node (ref "C383") (pin "2") (pinfunction "2_2") (pintype "passive"))
      (node (ref "FR58") (pin "2") (pinfunction "2_2") (pintype "passive"))
      (node (ref "IC28") (pin "5") (pinfunction "EN_5") (pintype "input"))
      (node (ref "IC28") (pin "8") (pinfunction "IN_8") (pintype "input"))
    )
    (net (code "19") (name "Net-(IC28-OUT)") (class "Default")
      (node (ref "C384") (pin "2") (pinfunction "2_2") (pintype "passive"))
      (node (ref "IC28") (pin "1") (pinfunction "OUT_1") (pintype "output"))
      (node (ref "R178") (pin "2") (pinfunction "2_2") (pintype "passive"))
      (node (ref "R179") (pin "2") (pinfunction "2_2") (pintype "passive"))
    )
    (net (code "20") (name "Net-(IC30-ADJ{slash}NC)") (class "Default")
      (node (ref "IC30") (pin "3") (pinfunction "ADJ/NC_3") (pintype "passive"))
      (node (ref "R189") (pin "2") (pinfunction "2_2") (pintype "passive"))
      (node (ref "R190") (pin "2") (pinfunction "2_2") (pintype "passive"))
    )
    (net (code "21") (name "Net-(IC30-EN)") (class "Default")
      (node (ref "C397") (pin "2") (pinfunction "2_2") (pintype "passive"))
      (node (ref "FR59") (pin "2") (pinfunction "2_2") (pintype "passive"))
      (node (ref "IC30") (pin "5") (pinfunction "EN_5") (pintype "input"))
      (node (ref "IC30") (pin "8") (pinfunction "IN_8") (pintype "input"))
    )
    (net (code "22") (name "Net-(IC30-OUT)") (class "Default")
      (node (ref "C398") (pin "2") (pinfunction "2_2") (pintype "passive"))
      (node (ref "IC30") (pin "1") (pinfunction "OUT_1") (pintype "output"))
      (node (ref "R188") (pin "2") (pinfunction "2_2") (pintype "passive"))
      (node (ref "R189") (pin "1") (pinfunction "1_1") (pintype "passive"))
    )
    (net (code "23") (name "Net-(IC31-PH-Pad17)") (class "Default")
      (node (ref "IC31") (pin "17") (pinfunction "PH_17") (pintype "power_in"))
      (node (ref "IC31") (pin "18") (pinfunction "PH_18") (pintype "power_in"))
      (node (ref "IC31") (pin "19") (pinfunction "PH_19") (pintype "power_in"))
      (node (ref "IC31") (pin "20") (pinfunction "PH_20") (pintype "power_in"))
      (node (ref "IC31") (pin "21") (pinfunction "PH_21") (pintype "power_in"))
      (node (ref "IC31") (pin "22") (pinfunction "PH_22") (pintype "power_in"))
      (node (ref "IC31") (pin "23") (pinfunction "PH_23") (pintype "power_in"))
      (node (ref "IC31") (pin "24") (pinfunction "PH_24") (pintype "power_in"))
      (node (ref "IC31") (pin "25") (pinfunction "PH_25") (pintype "power_in"))
      (node (ref "IC31") (pin "39") (pinfunction "PH_39") (pintype "power_in"))
    )
    (net (code "24") (name "Net-(IC31-RT{slash}CLK)") (class "Default")
      (node (ref "IC31") (pin "4") (pinfunction "RT/CLK_4") (pintype "input"))
      (node (ref "R184") (pin "2") (pinfunction "2_2") (pintype "passive"))
    )
    (net (code "25") (name "Net-(IC31-VADJ)") (class "Default")
      (node (ref "IC31") (pin "35") (pinfunction "VADJ_35") (pintype "input"))
      (node (ref "R183") (pin "2") (pinfunction "2_2") (pintype "passive"))
    )
    (net (code "26") (name "Net-(IC32-ADJ{slash}NC)") (class "Default")
      (node (ref "IC32") (pin "3") (pinfunction "ADJ/NC_3") (pintype "passive"))
      (node (ref "R193") (pin "1") (pinfunction "1_1") (pintype "passive"))
      (node (ref "R197") (pin "1") (pinfunction "1_1") (pintype "passive"))
    )
    (net (code "27") (name "Net-(IC32-OUT)") (class "Default")
      (node (ref "C402") (pin "2") (pinfunction "2_2") (pintype "passive"))
      (node (ref "IC32") (pin "1") (pinfunction "OUT_1") (pintype "output"))
      (node (ref "R191") (pin "2") (pinfunction "2_2") (pintype "passive"))
      (node (ref "R193") (pin "2") (pinfunction "2_2") (pintype "passive"))
    )
    (net (code "28") (name "Net-(IC33-ADJ{slash}NC)") (class "Default")
      (node (ref "IC33") (pin "3") (pinfunction "ADJ/NC_3") (pintype "passive"))
      (node (ref "R194") (pin "1") (pinfunction "1_1") (pintype "passive"))
      (node (ref "R198") (pin "2") (pinfunction "2_2") (pintype "passive"))
    )
    (net (code "29") (name "Net-(IC33-EN)") (class "Default")
      (node (ref "C404") (pin "2") (pinfunction "2_2") (pintype "passive"))
      (node (ref "FR60") (pin "2") (pinfunction "2_2") (pintype "passive"))
      (node (ref "IC33") (pin "5") (pinfunction "EN_5") (pintype "input"))
      (node (ref "IC33") (pin "8") (pinfunction "IN_8") (pintype "input"))
    )
    (net (code "30") (name "Net-(IC33-OUT)") (class "Default")
      (node (ref "C405") (pin "2") (pinfunction "2_2") (pintype "passive"))
      (node (ref "IC33") (pin "1") (pinfunction "OUT_1") (pintype "output"))
      (node (ref "R192") (pin "2") (pinfunction "2_2") (pintype "passive"))
      (node (ref "R194") (pin "2") (pinfunction "2_2") (pintype "passive"))
    )
    (net (code "31") (name "Net-(IC34-ADJ{slash}NC)") (class "Default")
      (node (ref "IC34") (pin "3") (pinfunction "ADJ/NC_3") (pintype "passive"))
      (node (ref "R203") (pin "1") (pinfunction "1_1") (pintype "passive"))
      (node (ref "R206") (pin "1") (pinfunction "1_1") (pintype "passive"))
    )
    (net (code "32") (name "Net-(IC34-OUT)") (class "Default")
      (node (ref "C410") (pin "2") (pinfunction "2_2") (pintype "passive"))
      (node (ref "IC34") (pin "1") (pinfunction "OUT_1") (pintype "output"))
      (node (ref "R202") (pin "2") (pinfunction "2_2") (pintype "passive"))
      (node (ref "R203") (pin "2") (pinfunction "2_2") (pintype "passive"))
    )
    (net (code "33") (name "Net-(IC35-ADJUST)") (class "Default")
      (node (ref "IC35") (pin "5") (pinfunction "ADJUST_5") (pintype "passive"))
      (node (ref "R205") (pin "2") (pinfunction "2_2") (pintype "passive"))
      (node (ref "R207") (pin "1") (pinfunction "1_1") (pintype "passive"))
    )
    (net (code "34") (name "Net-(IC35-IN)") (class "Default")
      (node (ref "C416") (pin "2") (pinfunction "2_2") (pintype "passive"))
      (node (ref "FR61") (pin "2") (pinfunction "2_2") (pintype "passive"))
      (node (ref "IC35") (pin "2") (pinfunction "IN_2") (pintype "passive"))
    )
    (net (code "35") (name "Net-(IC35-OUT)") (class "Default")
      (node (ref "C415") (pin "2") (pinfunction "2_2") (pintype "passive"))
      (node (ref "IC35") (pin "4") (pinfunction "OUT_4") (pintype "passive"))
      (node (ref "R204") (pin "2") (pinfunction "2_2") (pintype "passive"))
      (node (ref "R205") (pin "1") (pinfunction "1_1") (pintype "passive"))
    )
    (net (code "36") (name "Net-(IC36-ADJ{slash}BYP)") (class "Default")
      (node (ref "IC36") (pin "8") (pinfunction "ADJ/BYP_8") (pintype "input"))
      (node (ref "R209") (pin "2") (pinfunction "2_2") (pintype "passive"))
      (node (ref "R210") (pin "2") (pinfunction "2_2") (pintype "passive"))
    )
    (net (code "37") (name "Net-(IC36-EN)") (class "Default")
      (node (ref "C421") (pin "2") (pinfunction "2_2") (pintype "passive"))
      (node (ref "IC36") (pin "1") (pinfunction "EN_1") (pintype "input"))
      (node (ref "R211") (pin "2") (pinfunction "2_2") (pintype "passive"))
    )
    (net (code "38") (name "Net-(IC36-VIN)") (class "Default")
      (node (ref "C420") (pin "2") (pinfunction "2_2") (pintype "passive"))
      (node (ref "FR62") (pin "2") (pinfunction "2_2") (pintype "passive"))
      (node (ref "IC36") (pin "3") (pinfunction "VIN_3") (pintype "input"))
    )
    (net (code "39") (name "Net-(IC36-VOUT)") (class "Default")
      (node (ref "C417") (pin "2") (pinfunction "2_2") (pintype "passive"))
      (node (ref "FR63") (pin "1") (pinfunction "1_1") (pintype "passive"))
      (node (ref "IC36") (pin "5") (pinfunction "VOUT_5") (pintype "output"))
      (node (ref "R209") (pin "1") (pinfunction "1_1") (pintype "passive"))
    )
    (net (code "40") (name "Net-(IC45-ADJ{slash}NC)") (class "Default")
      (node (ref "IC45") (pin "3") (pinfunction "ADJ/NC_3") (pintype "passive"))
      (node (ref "R195") (pin "1") (pinfunction "1_1") (pintype "passive"))
      (node (ref "R196") (pin "2") (pinfunction "2_2") (pintype "passive"))
    )
    (net (code "41") (name "Net-(IC45-OUT)") (class "Default")
      (node (ref "C399") (pin "2") (pinfunction "2_2") (pintype "passive"))
      (node (ref "IC45") (pin "1") (pinfunction "OUT_1") (pintype "output"))
      (node (ref "R185") (pin "2") (pinfunction "2_2") (pintype "passive"))
      (node (ref "R195") (pin "2") (pinfunction "2_2") (pintype "passive"))
    )
    (net (code "42") (name "Net-(IC46-FB)") (class "Default")
      (node (ref "C413") (pin "1") (pinfunction "1_1") (pintype "passive"))
      (node (ref "IC46") (pin "8") (pinfunction "FB_8") (pintype "power_in"))
      (node (ref "R199") (pin "1") (pinfunction "1_1") (pintype "passive"))
      (node (ref "R200") (pin "2") (pinfunction "2_2") (pintype "passive"))
    )
    (net (code "43") (name "Net-(IC46-L1)") (class "Default")
      (node (ref "IC46") (pin "1") (pinfunction "L1_1") (pintype "power_in"))
      (node (ref "L2") (pin "1") (pinfunction "1_1") (pintype "passive"))
    )
    (net (code "44") (name "Net-(IC46-L2)") (class "Default")
      (node (ref "IC46") (pin "10") (pinfunction "L2_10") (pintype "power_in"))
      (node (ref "L2") (pin "2") (pinfunction "2_2") (pintype "passive"))
    )
    (net (code "45") (name "Net-(IC46-VAUX)") (class "Default")
      (node (ref "C412") (pin "2") (pinfunction "2_2") (pintype "passive"))
      (node (ref "IC46") (pin "6") (pinfunction "VAUX_6") (pintype "power_in"))
    )
    (net (code "46") (name "VCC2P5") (class "Default")
      (node (ref "R173") (pin "1") (pinfunction "1_1") (pintype "passive"))
      (node (ref "R211") (pin "1") (pinfunction "1_1") (pintype "passive"))
    )
    (net (code "47") (name "VCC3P3") (class "Default")
      (node (ref "C376") (pin "2") (pinfunction "2_2") (pintype "passive"))
      (node (ref "C379") (pin "1") (pinfunction "1_1") (pintype "passive"))
      (node (ref "C382") (pin "2") (pinfunction "2_2") (pintype "passive"))
      (node (ref "C386") (pin "2") (pinfunction "2_2") (pintype "passive"))
      (node (ref "C396") (pin "2") (pinfunction "2_2") (pintype "passive"))
      (node (ref "C401") (pin "2") (pinfunction "2_2") (pintype "passive"))
      (node (ref "C403") (pin "2") (pinfunction "2_2") (pintype "passive"))
      (node (ref "C409") (pin "2") (pinfunction "2_2") (pintype "passive"))
      (node (ref "C414") (pin "2") (pinfunction "2_2") (pintype "passive"))
      (node (ref "FR58") (pin "1") (pinfunction "1_1") (pintype "passive"))
      (node (ref "FR59") (pin "1") (pinfunction "1_1") (pintype "passive"))
      (node (ref "FR60") (pin "1") (pinfunction "1_1") (pintype "passive"))
      (node (ref "FR61") (pin "1") (pinfunction "1_1") (pintype "passive"))
      (node (ref "IC26") (pin "5") (pinfunction "EN_5") (pintype "input"))
      (node (ref "IC26") (pin "8") (pinfunction "IN_8") (pintype "input"))
      (node (ref "IC27") (pin "10") (pinfunction "VOUT_10") (pintype "power_in"))
      (node (ref "IC27") (pin "11") (pinfunction "VOUT_11") (pintype "power_in"))
      (node (ref "IC27") (pin "12") (pinfunction "VOUT_12") (pintype "power_in"))
      (node (ref "IC27") (pin "13") (pinfunction "VOUT_13") (pintype "power_in"))
      (node (ref "IC27") (pin "14") (pinfunction "VOUT_14") (pintype "power_in"))
      (node (ref "IC27") (pin "36") (pinfunction "SENSE+_36") (pintype "input"))
      (node (ref "IC27") (pin "38") (pinfunction "VOUT_38") (pintype "power_in"))
      (node (ref "IC27") (pin "8") (pinfunction "VOUT_8") (pintype "power_in"))
      (node (ref "IC27") (pin "9") (pinfunction "VOUT_9") (pintype "power_in"))
      (node (ref "IC32") (pin "5") (pinfunction "EN_5") (pintype "input"))
      (node (ref "IC32") (pin "8") (pinfunction "IN_8") (pintype "input"))
      (node (ref "IC34") (pin "5") (pinfunction "EN_5") (pintype "input"))
      (node (ref "IC34") (pin "8") (pinfunction "IN_8") (pintype "input"))
    )
    (net (code "48") (name "VCC6P0") (class "Default")
      (node (ref "C400") (pin "2") (pinfunction "2_2") (pintype "passive"))
      (node (ref "C407") (pin "2") (pinfunction "2_2") (pintype "passive"))
      (node (ref "C408") (pin "2") (pinfunction "2_2") (pintype "passive"))
      (node (ref "C411") (pin "2") (pinfunction "2_2") (pintype "passive"))
      (node (ref "IC45") (pin "5") (pinfunction "EN_5") (pintype "input"))
      (node (ref "IC45") (pin "8") (pinfunction "IN_8") (pintype "input"))
      (node (ref "IC46") (pin "9") (pinfunction "VOUT_9") (pintype "power_in"))
      (node (ref "R199") (pin "2") (pinfunction "2_2") (pintype "passive"))
    )
    (net (code "49") (name "VCC_SYS") (class "Default")
      (node (ref "C385") (pin "1") (pinfunction "1_1") (pintype "passive"))
      (node (ref "C388") (pin "2") (pinfunction "2_2") (pintype "passive"))
      (node (ref "C389") (pin "1") (pinfunction "1_1") (pintype "passive"))
      (node (ref "C390") (pin "2") (pinfunction "2_2") (pintype "passive"))
      (node (ref "C406") (pin "1") (pinfunction "1_1") (pintype "passive"))
      (node (ref "C419") (pin "2") (pinfunction "2_2") (pintype "passive"))
      (node (ref "FR62") (pin "1") (pinfunction "1_1") (pintype "passive"))
      (node (ref "IC27") (pin "30") (pinfunction "VIN_30") (pintype "power_in"))
      (node (ref "IC27") (pin "31") (pinfunction "VIN_31") (pintype "power_in"))
      (node (ref "IC27") (pin "32") (pinfunction "VIN_32") (pintype "power_in"))
      (node (ref "IC31") (pin "30") (pinfunction "VIN_30") (pintype "power_in"))
      (node (ref "IC31") (pin "31") (pinfunction "VIN_31") (pintype "power_in"))
      (node (ref "IC31") (pin "32") (pinfunction "VIN_32") (pintype "power_in"))
      (node (ref "IC46") (pin "2") (pinfunction "VIN_2") (pintype "power_in"))
      (node (ref "IC46") (pin "3") (pinfunction "EN_3") (pintype "power_in"))
    )
    (net (code "50") (name "unconnected-(F1-Pad1)") (class "Default")
      (node (ref "F1") (pin "1") (pintype "passive+no_connect"))
    )
    (net (code "51") (name "unconnected-(F2-Pad1)") (class "Default")
      (node (ref "F2") (pin "1") (pintype "passive+no_connect"))
    )
    (net (code "52") (name "unconnected-(F3-Pad1)") (class "Default")
      (node (ref "F3") (pin "1") (pintype "passive+no_connect"))
    )
    (net (code "53") (name "unconnected-(F4-Pad1)") (class "Default")
      (node (ref "F4") (pin "1") (pintype "passive+no_connect"))
    )
    (net (code "54") (name "unconnected-(IC26-NC-Pad2)") (class "Default")
      (node (ref "IC26") (pin "2") (pinfunction "NC_2") (pintype "passive+no_connect"))
    )
    (net (code "55") (name "unconnected-(IC26-NC-Pad6)") (class "Default")
      (node (ref "IC26") (pin "6") (pinfunction "NC_6") (pintype "passive+no_connect"))
    )
    (net (code "56") (name "unconnected-(IC26-NC-Pad7)") (class "Default")
      (node (ref "IC26") (pin "7") (pinfunction "NC_7") (pintype "passive+no_connect"))
    )
    (net (code "57") (name "unconnected-(IC27-DNC-Pad2)") (class "Default")
      (node (ref "IC27") (pin "2") (pinfunction "DNC_2") (pintype "passive+no_connect"))
    )
    (net (code "58") (name "unconnected-(IC27-DNC-Pad3)") (class "Default")
      (node (ref "IC27") (pin "3") (pinfunction "DNC_3") (pintype "passive+no_connect"))
    )
    (net (code "59") (name "unconnected-(IC27-DNC-Pad15)") (class "Default")
      (node (ref "IC27") (pin "15") (pinfunction "DNC_15") (pintype "passive+no_connect"))
    )
    (net (code "60") (name "unconnected-(IC27-DNC-Pad16)") (class "Default")
      (node (ref "IC27") (pin "16") (pinfunction "DNC_16") (pintype "passive+no_connect"))
    )
    (net (code "61") (name "unconnected-(IC27-DNC-Pad26)") (class "Default")
      (node (ref "IC27") (pin "26") (pinfunction "DNC_26") (pintype "passive+no_connect"))
    )
    (net (code "62") (name "unconnected-(IC27-INH{slash}UVLO-Pad28)") (class "Default")
      (node (ref "IC27") (pin "28") (pinfunction "INH/UVLO_28") (pintype "input+no_connect"))
    )
    (net (code "63") (name "unconnected-(IC27-PWRGD-Pad27)") (class "Default")
      (node (ref "IC27") (pin "27") (pinfunction "PWRGD_27") (pintype "output+no_connect"))
    )
    (net (code "64") (name "unconnected-(IC27-SS{slash}TR-Pad6)") (class "Default")
      (node (ref "IC27") (pin "6") (pinfunction "SS/TR_6") (pintype "input+no_connect"))
    )
    (net (code "65") (name "unconnected-(IC28-NC-Pad2)") (class "Default")
      (node (ref "IC28") (pin "2") (pinfunction "NC_2") (pintype "passive+no_connect"))
    )
    (net (code "66") (name "unconnected-(IC28-NC-Pad6)") (class "Default")
      (node (ref "IC28") (pin "6") (pinfunction "NC_6") (pintype "passive+no_connect"))
    )
    (net (code "67") (name "unconnected-(IC28-NC-Pad7)") (class "Default")
      (node (ref "IC28") (pin "7") (pinfunction "NC_7") (pintype "passive+no_connect"))
    )
    (net (code "68") (name "unconnected-(IC30-NC-Pad2)") (class "Default")
      (node (ref "IC30") (pin "2") (pinfunction "NC_2") (pintype "passive+no_connect"))
    )
    (net (code "69") (name "unconnected-(IC30-NC-Pad6)") (class "Default")
      (node (ref "IC30") (pin "6") (pinfunction "NC_6") (pintype "passive+no_connect"))
    )
    (net (code "70") (name "unconnected-(IC30-NC-Pad7)") (class "Default")
      (node (ref "IC30") (pin "7") (pinfunction "NC_7") (pintype "passive+no_connect"))
    )
    (net (code "71") (name "unconnected-(IC31-DNC-Pad2)") (class "Default")
      (node (ref "IC31") (pin "2") (pinfunction "DNC_2") (pintype "passive+no_connect"))
    )
    (net (code "72") (name "unconnected-(IC31-DNC-Pad3)") (class "Default")
      (node (ref "IC31") (pin "3") (pinfunction "DNC_3") (pintype "passive+no_connect"))
    )
    (net (code "73") (name "unconnected-(IC31-DNC-Pad15)") (class "Default")
      (node (ref "IC31") (pin "15") (pinfunction "DNC_15") (pintype "passive+no_connect"))
    )
    (net (code "74") (name "unconnected-(IC31-DNC-Pad16)") (class "Default")
      (node (ref "IC31") (pin "16") (pinfunction "DNC_16") (pintype "passive+no_connect"))
    )
    (net (code "75") (name "unconnected-(IC31-DNC-Pad26)") (class "Default")
      (node (ref "IC31") (pin "26") (pinfunction "DNC_26") (pintype "passive+no_connect"))
    )
    (net (code "76") (name "unconnected-(IC31-INH{slash}UVLO-Pad28)") (class "Default")
      (node (ref "IC31") (pin "28") (pinfunction "INH/UVLO_28") (pintype "input+no_connect"))
    )
    (net (code "77") (name "unconnected-(IC31-PWRGD-Pad27)") (class "Default")
      (node (ref "IC31") (pin "27") (pinfunction "PWRGD_27") (pintype "output+no_connect"))
    )
    (net (code "78") (name "unconnected-(IC31-SS{slash}TR-Pad6)") (class "Default")
      (node (ref "IC31") (pin "6") (pinfunction "SS/TR_6") (pintype "input+no_connect"))
    )
    (net (code "79") (name "unconnected-(IC32-NC-Pad2)") (class "Default")
      (node (ref "IC32") (pin "2") (pinfunction "NC_2") (pintype "passive+no_connect"))
    )
    (net (code "80") (name "unconnected-(IC32-NC-Pad6)") (class "Default")
      (node (ref "IC32") (pin "6") (pinfunction "NC_6") (pintype "passive+no_connect"))
    )
    (net (code "81") (name "unconnected-(IC32-NC-Pad7)") (class "Default")
      (node (ref "IC32") (pin "7") (pinfunction "NC_7") (pintype "passive+no_connect"))
    )
    (net (code "82") (name "unconnected-(IC33-NC-Pad2)") (class "Default")
      (node (ref "IC33") (pin "2") (pinfunction "NC_2") (pintype "passive+no_connect"))
    )
    (net (code "83") (name "unconnected-(IC33-NC-Pad6)") (class "Default")
      (node (ref "IC33") (pin "6") (pinfunction "NC_6") (pintype "passive+no_connect"))
    )
    (net (code "84") (name "unconnected-(IC33-NC-Pad7)") (class "Default")
      (node (ref "IC33") (pin "7") (pinfunction "NC_7") (pintype "passive+no_connect"))
    )
    (net (code "85") (name "unconnected-(IC34-NC-Pad2)") (class "Default")
      (node (ref "IC34") (pin "2") (pinfunction "NC_2") (pintype "passive+no_connect"))
    )
    (net (code "86") (name "unconnected-(IC34-NC-Pad6)") (class "Default")
      (node (ref "IC34") (pin "6") (pinfunction "NC_6") (pintype "passive+no_connect"))
    )
    (net (code "87") (name "unconnected-(IC34-NC-Pad7)") (class "Default")
      (node (ref "IC34") (pin "7") (pinfunction "NC_7") (pintype "passive+no_connect"))
    )
    (net (code "88") (name "unconnected-(IC35-NC-Pad1)") (class "Default")
      (node (ref "IC35") (pin "1") (pinfunction "NC_1") (pintype "passive+no_connect"))
    )
    (net (code "89") (name "unconnected-(IC36-NC-Pad2)") (class "Default")
      (node (ref "IC36") (pin "2") (pinfunction "NC_2") (pintype "passive+no_connect"))
    )
    (net (code "90") (name "unconnected-(IC36-NC-Pad4)") (class "Default")
      (node (ref "IC36") (pin "4") (pinfunction "NC_4") (pintype "passive+no_connect"))
    )
    (net (code "91") (name "unconnected-(IC36-NC-Pad6)") (class "Default")
      (node (ref "IC36") (pin "6") (pinfunction "NC_6") (pintype "passive+no_connect"))
    )
    (net (code "92") (name "unconnected-(IC45-NC-Pad2)") (class "Default")
      (node (ref "IC45") (pin "2") (pinfunction "NC_2") (pintype "passive+no_connect"))
    )
    (net (code "93") (name "unconnected-(IC45-NC-Pad6)") (class "Default")
      (node (ref "IC45") (pin "6") (pinfunction "NC_6") (pintype "passive+no_connect"))
    )
    (net (code "94") (name "unconnected-(IC45-NC-Pad7)") (class "Default")
      (node (ref "IC45") (pin "7") (pinfunction "NC_7") (pintype "passive+no_connect"))
    )
    (net (code "95") (name "unconnected-(IC46-PG-Pad5)") (class "Default")
      (node (ref "IC46") (pin "5") (pinfunction "PG_5") (pintype "power_in+no_connect"))
    )
  )
)
